# DevCard_V1.net
KiCad netlist of a schematic drawn in Altium Designer
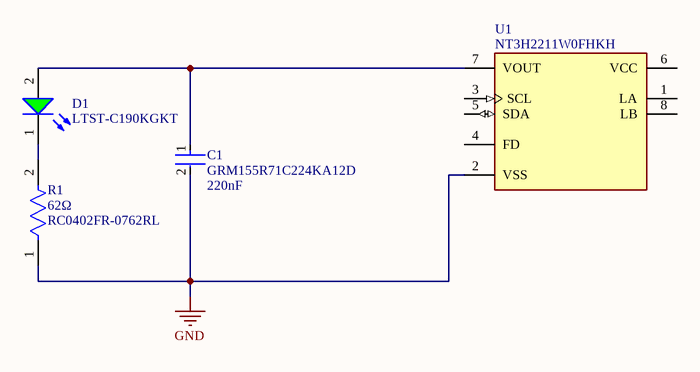
[diagram p0: DevCard_V1.SchDoc]

(export (version "E")
  (design (tool "Eeschema 10.0.6"))
  (components
    (comp (ref "C1")
      (value "GRM155R71C224KA12D")
      (footprint "GRM155-0402-MFG")
      (description "220nF 0402 Multilayer Ceramic Capacitor")
      (fields
        (field (name "LCSC PART NUMBER") "C77011")
        (field (name "MANUFACTURER PART NUMBER") "GRM155R71C224KA12D")
        (field (name "CAPACITANCE") "220nF")
      )
      (libsource (lib "Library") (part "GRM155R71C224KA12D"))
    )
    (comp (ref "D1")
      (value "LTST-C190KGKT")
      (footprint "FP-LTST-C190KGKT-MFG")
      (description "LED Emerald 2V 0603")
      (fields
        (field (name "LCSC PART NUMBER") "C125094")
        (field (name "MANUFACTURER PART NUMBER") "LTST-C190KGKT")
      )
      (libsource (lib "Library") (part "LTST-C190KGKT"))
    )
    (comp (ref "R1")
      (value "RC0402FR-0762RL")
      (footprint "RC0402-MFG")
      (description "62Ω 0402 Chip Resistor")
      (fields
        (field (name "LCSC PART NUMBER") "C274896")
        (field (name "RESISTANCE") "62Ω")
        (field (name "MANUFACTURER PART NUMBER") "RC0402FR-0762RL")
      )
      (libsource (lib "Library") (part "RC0402FR-0762RL"))
    )
    (comp (ref "U1")
      (value "NT3H2211W0FHKH")
      (footprint "FP-SOT902-3-MFG")
      (description "IC RFID TRANSP 13.56MHZ 8XQFN")
      (libsource (lib "Altium Content Vault") (part "2b1fb85705dcb3754108af1b35d4811"))
    )
  )
  (nets
    (net (code "1") (name "GND") (class "Default")
      (node (ref "C1") (pin "2") (pinfunction "2_2") (pintype "passive"))
      (node (ref "R1") (pin "1") (pinfunction "1_1") (pintype "passive"))
      (node (ref "U1") (pin "2") (pinfunction "VSS_2") (pintype "power_in"))
    )
    (net (code "2") (name "Net-(D1-A)") (class "Default")
      (node (ref "C1") (pin "1") (pinfunction "1_1") (pintype "passive"))
      (node (ref "D1") (pin "2") (pinfunction "A_2") (pintype "passive"))
      (node (ref "U1") (pin "7") (pinfunction "VOUT_7") (pintype "power_in"))
    )
    (net (code "3") (name "Net-(D1-K)") (class "Default")
      (node (ref "D1") (pin "1") (pinfunction "K_1") (pintype "passive"))
      (node (ref "R1") (pin "2") (pinfunction "2_2") (pintype "passive"))
    )
    (net (code "4") (name "unconnected-(U1-FD-Pad4)") (class "Default")
      (node (ref "U1") (pin "4") (pinfunction "FD_4") (pintype "passive"))
    )
    (net (code "5") (name "unconnected-(U1-LA-Pad1)") (class "Default")
      (node (ref "U1") (pin "1") (pinfunction "LA_1") (pintype "passive"))
    )
    (net (code "6") (name "unconnected-(U1-LB-Pad8)") (class "Default")
      (node (ref "U1") (pin "8") (pinfunction "LB_8") (pintype "passive"))
    )
    (net (code "7") (name "unconnected-(U1-SCL-Pad3)") (class "Default")
      (node (ref "U1") (pin "3") (pinfunction "SCL_3") (pintype "input"))
    )
    (net (code "8") (name "unconnected-(U1-SDA-Pad5)") (class "Default")
      (node (ref "U1") (pin "5") (pinfunction "SDA_5") (pintype "bidirectional"))
    )
    (net (code "9") (name "unconnected-(U1-VCC-Pad6)") (class "Default")
      (node (ref "U1") (pin "6") (pinfunction "VCC_6") (pintype "power_in"))
    )
  )
)
